# MAM_GND.net
KiCad netlist of a schematic drawn in EAGLE
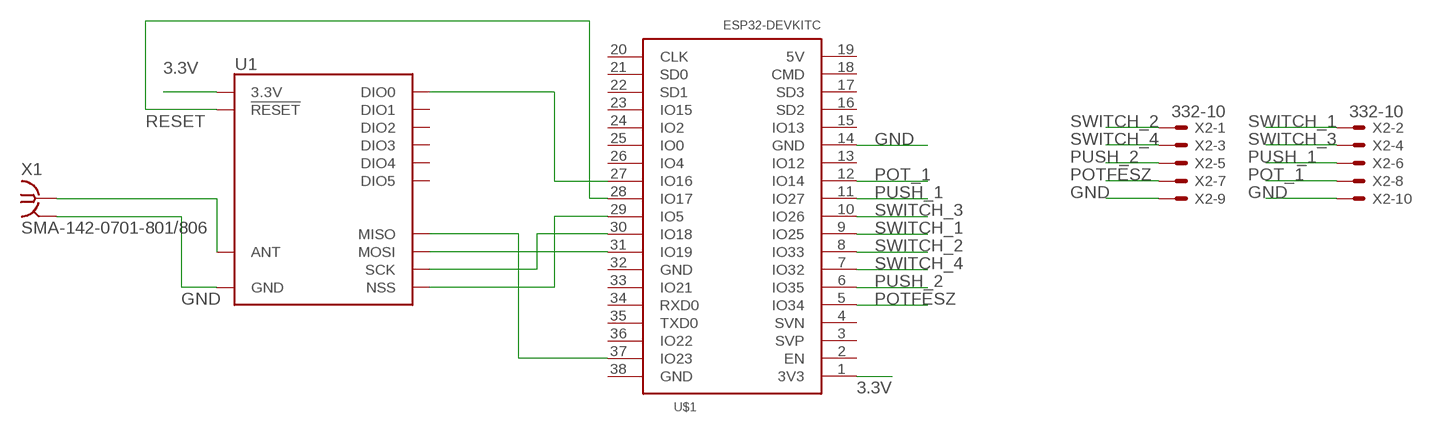
[diagram p0: schematic, sheet 1]

(export (version "E")
  (design (tool "Eeschema 10.0.6"))
  (components
    (comp (ref "U$1")
      (value "ESP32DEVKITC")
      (footprint "eagle-import:ESP32-DEVKITC")
      (libsource (lib "eagle-import") (part "ESP32DEVKITC"))
    )
    (comp (ref "U1")
      (value "RFM95W")
      (footprint "eagle-import:RFM95_96_97_98W")
      (libsource (lib "eagle-import") (part "RFM95W"))
    )
    (comp (ref "X1")
      (value "SMA-142-0701-801/806")
      (footprint "eagle-import:J502-ND-142-0701-801_806")
      (fields (field (name "MF") "JOHNSON COMPONENTS") (field (name "MPN") "142-0701-801"))
      (libsource (lib "eagle-import") (part "SMA-142-0701-801/806"))
    )
    (comp (ref "X2")
      (value "332-10")
      (footprint "eagle-import:332-10")
      (libsource (lib "eagle-import") (part "332-10"))
    )
  )
  (nets
    (net (code "1") (name "/3.3V") (class "Default")
      (node (ref "U$1") (pin "1") (pinfunction "3V3_1") (pintype "bidirectional"))
      (node (ref "U1") (pin "3.3V") (pinfunction "3.3V_3.3V") (pintype "bidirectional"))
    )
    (net (code "2") (name "/GND") (class "Default")
      (node (ref "U$1") (pin "14") (pinfunction "GND_14") (pintype "bidirectional"))
      (node (ref "U1") (pin "GND@1") (pinfunction "GND_GND@1") (pintype "bidirectional"))
      (node (ref "U1") (pin "GND@2") (pinfunction "GND_GND@2") (pintype "bidirectional"))
      (node (ref "U1") (pin "GND@3") (pinfunction "GND_GND@3") (pintype "bidirectional"))
      (node (ref "X1") (pin "G@1") (pinfunction "2_G@1") (pintype "passive"))
      (node (ref "X1") (pin "G@2") (pinfunction "2_G@2") (pintype "passive"))
      (node (ref "X1") (pin "G@3") (pinfunction "2_G@3") (pintype "passive"))
      (node (ref "X1") (pin "G@4") (pinfunction "2_G@4") (pintype "passive"))
      (node (ref "X2") (pin "10") (pinfunction "S_10") (pintype "passive"))
      (node (ref "X2") (pin "9") (pinfunction "S_9") (pintype "passive"))
    )
    (net (code "3") (name "/POTFESZ") (class "Default")
      (node (ref "U$1") (pin "5") (pinfunction "IO34_5") (pintype "bidirectional"))
      (node (ref "X2") (pin "7") (pinfunction "S_7") (pintype "passive"))
    )
    (net (code "4") (name "/POT_1") (class "Default")
      (node (ref "U$1") (pin "12") (pinfunction "IO14_12") (pintype "bidirectional"))
      (node (ref "X2") (pin "8") (pinfunction "S_8") (pintype "passive"))
    )
    (net (code "5") (name "/PUSH_1") (class "Default")
      (node (ref "U$1") (pin "11") (pinfunction "IO27_11") (pintype "bidirectional"))
      (node (ref "X2") (pin "6") (pinfunction "S_6") (pintype "passive"))
    )
    (net (code "6") (name "/PUSH_2") (class "Default")
      (node (ref "U$1") (pin "6") (pinfunction "IO35_6") (pintype "bidirectional"))
      (node (ref "X2") (pin "5") (pinfunction "S_5") (pintype "passive"))
    )
    (net (code "7") (name "/RESET") (class "Default")
      (node (ref "U$1") (pin "28") (pinfunction "IO17_28") (pintype "bidirectional"))
      (node (ref "U1") (pin "!RESET") (pinfunction "~{RESET}_!RESET") (pintype "bidirectional"))
    )
    (net (code "8") (name "/SWITCH_1") (class "Default")
      (node (ref "U$1") (pin "9") (pinfunction "IO25_9") (pintype "bidirectional"))
      (node (ref "X2") (pin "2") (pinfunction "S_2") (pintype "passive"))
    )
    (net (code "9") (name "/SWITCH_2") (class "Default")
      (node (ref "U$1") (pin "8") (pinfunction "IO33_8") (pintype "bidirectional"))
      (node (ref "X2") (pin "1") (pinfunction "S_1") (pintype "passive"))
    )
    (net (code "10") (name "/SWITCH_3") (class "Default")
      (node (ref "U$1") (pin "10") (pinfunction "IO26_10") (pintype "bidirectional"))
      (node (ref "X2") (pin "4") (pinfunction "S_4") (pintype "passive"))
    )
    (net (code "11") (name "/SWITCH_4") (class "Default")
      (node (ref "U$1") (pin "7") (pinfunction "IO32_7") (pintype "bidirectional"))
      (node (ref "X2") (pin "3") (pinfunction "S_3") (pintype "passive"))
    )
    (net (code "12") (name "Net-(U$1-IO5)") (class "Default")
      (node (ref "U$1") (pin "29") (pinfunction "IO5_29") (pintype "bidirectional"))
      (node (ref "U1") (pin "NSS") (pinfunction "NSS_NSS") (pintype "bidirectional"))
    )
    (net (code "13") (name "Net-(U$1-IO16)") (class "Default")
      (node (ref "U$1") (pin "27") (pinfunction "IO16_27") (pintype "bidirectional"))
      (node (ref "U1") (pin "DIO0") (pinfunction "DIO0_DIO0") (pintype "bidirectional"))
    )
    (net (code "14") (name "Net-(U$1-IO18)") (class "Default")
      (node (ref "U$1") (pin "30") (pinfunction "IO18_30") (pintype "bidirectional"))
      (node (ref "U1") (pin "SCK") (pinfunction "SCK_SCK") (pintype "bidirectional"))
    )
    (net (code "15") (name "Net-(U$1-IO19)") (class "Default")
      (node (ref "U$1") (pin "31") (pinfunction "IO19_31") (pintype "bidirectional"))
      (node (ref "U1") (pin "MOSI") (pinfunction "MOSI_MOSI") (pintype "bidirectional"))
    )
    (net (code "16") (name "Net-(U$1-IO23)") (class "Default")
      (node (ref "U$1") (pin "37") (pinfunction "IO23_37") (pintype "bidirectional"))
      (node (ref "U1") (pin "MISO") (pinfunction "MISO_MISO") (pintype "bidirectional"))
    )
    (net (code "17") (name "Net-(U1-PadANT)") (class "Default")
      (node (ref "U1") (pin "ANT") (pinfunction "ANT_ANT") (pintype "bidirectional"))
      (node (ref "X1") (pin "1") (pinfunction "1_1") (pintype "passive"))
    )
    (net (code "18") (name "unconnected-(U$1-5V-Pad19)") (class "Default")
      (node (ref "U$1") (pin "19") (pinfunction "5V_19") (pintype "bidirectional"))
    )
    (net (code "19") (name "unconnected-(U$1-CLK-Pad20)") (class "Default")
      (node (ref "U$1") (pin "20") (pinfunction "CLK_20") (pintype "bidirectional"))
    )
    (net (code "20") (name "unconnected-(U$1-CMD-Pad18)") (class "Default")
      (node (ref "U$1") (pin "18") (pinfunction "CMD_18") (pintype "bidirectional"))
    )
    (net (code "21") (name "unconnected-(U$1-EN-Pad2)") (class "Default")
      (node (ref "U$1") (pin "2") (pinfunction "EN_2") (pintype "bidirectional"))
    )
    (net (code "22") (name "unconnected-(U$1-GND-Pad32)") (class "Default")
      (node (ref "U$1") (pin "32") (pinfunction "GND_32") (pintype "bidirectional"))
    )
    (net (code "23") (name "unconnected-(U$1-GND-Pad38)") (class "Default")
      (node (ref "U$1") (pin "38") (pinfunction "GND_38") (pintype "bidirectional"))
    )
    (net (code "24") (name "unconnected-(U$1-IO0-Pad25)") (class "Default")
      (node (ref "U$1") (pin "25") (pinfunction "IO0_25") (pintype "bidirectional"))
    )
    (net (code "25") (name "unconnected-(U$1-IO2-Pad24)") (class "Default")
      (node (ref "U$1") (pin "24") (pinfunction "IO2_24") (pintype "bidirectional"))
    )
    (net (code "26") (name "unconnected-(U$1-IO4-Pad26)") (class "Default")
      (node (ref "U$1") (pin "26") (pinfunction "IO4_26") (pintype "bidirectional"))
    )
    (net (code "27") (name "unconnected-(U$1-IO12-Pad13)") (class "Default")
      (node (ref "U$1") (pin "13") (pinfunction "IO12_13") (pintype "bidirectional"))
    )
    (net (code "28") (name "unconnected-(U$1-IO13-Pad15)") (class "Default")
      (node (ref "U$1") (pin "15") (pinfunction "IO13_15") (pintype "bidirectional"))
    )
    (net (code "29") (name "unconnected-(U$1-IO15-Pad23)") (class "Default")
      (node (ref "U$1") (pin "23") (pinfunction "IO15_23") (pintype "bidirectional"))
    )
    (net (code "30") (name "unconnected-(U$1-IO21-Pad33)") (class "Default")
      (node (ref "U$1") (pin "33") (pinfunction "IO21_33") (pintype "bidirectional"))
    )
    (net (code "31") (name "unconnected-(U$1-IO22-Pad36)") (class "Default")
      (node (ref "U$1") (pin "36") (pinfunction "IO22_36") (pintype "bidirectional"))
    )
    (net (code "32") (name "unconnected-(U$1-RXD0-Pad34)") (class "Default")
      (node (ref "U$1") (pin "34") (pinfunction "RXD0_34") (pintype "bidirectional"))
    )
    (net (code "33") (name "unconnected-(U$1-SD0-Pad21)") (class "Default")
      (node (ref "U$1") (pin "21") (pinfunction "SD0_21") (pintype "bidirectional"))
    )
    (net (code "34") (name "unconnected-(U$1-SD1-Pad22)") (class "Default")
      (node (ref "U$1") (pin "22") (pinfunction "SD1_22") (pintype "bidirectional"))
    )
    (net (code "35") (name "unconnected-(U$1-SD2-Pad16)") (class "Default")
      (node (ref "U$1") (pin "16") (pinfunction "SD2_16") (pintype "bidirectional"))
    )
    (net (code "36") (name "unconnected-(U$1-SD3-Pad17)") (class "Default")
      (node (ref "U$1") (pin "17") (pinfunction "SD3_17") (pintype "bidirectional"))
    )
    (net (code "37") (name "unconnected-(U$1-SVN-Pad4)") (class "Default")
      (node (ref "U$1") (pin "4") (pinfunction "SVN_4") (pintype "bidirectional"))
    )
    (net (code "38") (name "unconnected-(U$1-SVP-Pad3)") (class "Default")
      (node (ref "U$1") (pin "3") (pinfunction "SVP_3") (pintype "bidirectional"))
    )
    (net (code "39") (name "unconnected-(U$1-TXD0-Pad35)") (class "Default")
      (node (ref "U$1") (pin "35") (pinfunction "TXD0_35") (pintype "bidirectional"))
    )
    (net (code "40") (name "unconnected-(U1-PadDIO1)") (class "Default")
      (node (ref "U1") (pin "DIO1") (pinfunction "DIO1_DIO1") (pintype "bidirectional"))
    )
    (net (code "41") (name "unconnected-(U1-PadDIO2)") (class "Default")
      (node (ref "U1") (pin "DIO2") (pinfunction "DIO2_DIO2") (pintype "bidirectional"))
    )
    (net (code "42") (name "unconnected-(U1-PadDIO3)") (class "Default")
      (node (ref "U1") (pin "DIO3") (pinfunction "DIO3_DIO3") (pintype "bidirectional"))
    )
    (net (code "43") (name "unconnected-(U1-PadDIO4)") (class "Default")
      (node (ref "U1") (pin "DIO4") (pinfunction "DIO4_DIO4") (pintype "bidirectional"))
    )
    (net (code "44") (name "unconnected-(U1-PadDIO5)") (class "Default")
      (node (ref "U1") (pin "DIO5") (pinfunction "DIO5_DIO5") (pintype "bidirectional"))
    )
  )
)
